# USB.net
KiCad netlist of a schematic drawn in Altium Designer
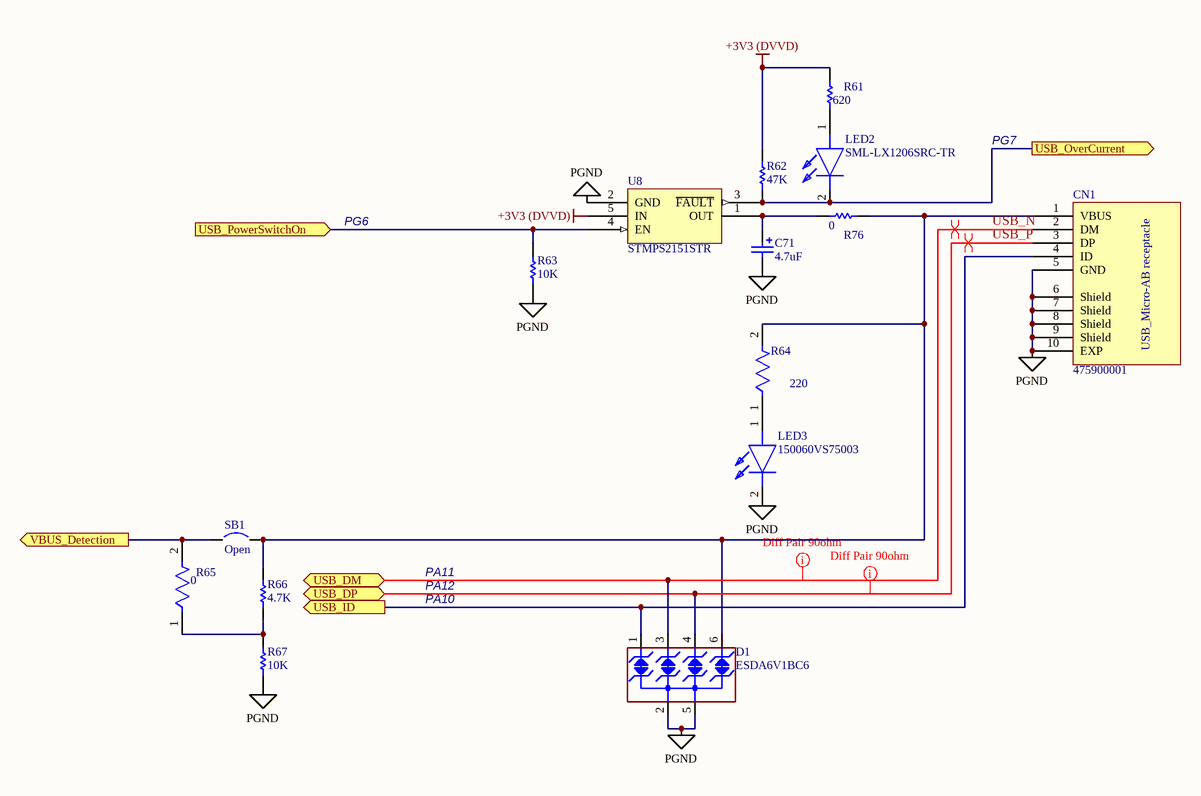
[diagram p0: USB.SchDoc]

(export (version "E")
  (design (tool "Eeschema 10.0.6"))
  (components
    (comp (ref "C71")
      (value "4.7uF")
      (footprint "Copy of MB1137:TAN-A")
      (description "Polarized Capacitor (Radial)")
      (fields (field (name "PUBLISHER") "Altium Limited"))
      (libsource (lib "Miscellaneous Devices") (part "Cap Pol1"))
    )
    (comp (ref "CN1")
      (value "475900001")
      (footprint "Copy of MB1137:MOLEX_47590001")
      (libsource (lib "Copy of MB1137") (part "475900001"))
    )
    (comp (ref "D1")
      (value "ESDA6V1BC6")
      (footprint "Copy of MB1137:3")
      (description "4-line ESD protection")
      (libsource (lib "Copy of MB1137") (part "ESDA6V1BC6"))
    )
    (comp (ref "LED2")
      (value "SML-LX1206SRC-TR")
      (footprint "SamacSys:SMLLX1206SRCTR")
      (description "LED")
      (fields (field (name "MOUSER PART NUMBER") "696-SML-LX1206SRC"))
      (libsource (lib "*") (part "SML-LX1206SRC-TR"))
    )
    (comp (ref "LED3")
      (value "150060VS75003")
      (footprint "SamacSys:150060VS75003")
      (description "LED")
      (fields (field (name "MOUSER PART NUMBER") "710-150060VS75003"))
      (libsource (lib "*") (part "150060VS75003"))
    )
    (comp (ref "R61")
      (value "620")
      (footprint "Copy of MB1137:0603R")
      (description "Resistor")
      (fields (field (name "PUBLISHER") "Altium Limited"))
      (libsource (lib "Miscellaneous Devices") (part "Res1"))
    )
    (comp (ref "R62")
      (value "47K")
      (footprint "Copy of MB1137:0603R")
      (description "Resistor")
      (fields (field (name "PUBLISHER") "Altium Limited"))
      (libsource (lib "Miscellaneous Devices") (part "res1"))
    )
    (comp (ref "R63")
      (value "10K")
      (footprint "Copy of MB1137:0603R")
      (description "Resistor")
      (fields (field (name "PUBLISHER") "Altium Limited"))
      (libsource (lib "Miscellaneous Devices") (part "Res1"))
    )
    (comp (ref "R64")
      (value "220")
      (footprint "FP-CRCW0805-e3-MFG")
      (description "RES Thick Film, 220Ω, 1%, 0.125W, 100ppm/°C, 0805")
      (fields (field (name "TOLERANCE") "1%"))
      (libsource (lib "Altium Content Vault") (part "1029c3af85768c4190bb7ad29bc67b5"))
    )
    (comp (ref "R65")
      (value "0")
      (footprint "FP-CRCW1206-MFG")
      (description "CRCW12060000ZSTA Zero Ohm Resistor, Jumper, 1206 [3216 Metric], Thick Film, 250 mW, Surface Mount")
      (libsource (lib "Altium Content Vault") (part "1029c3af85768c4190bb7ad29bc67b5"))
    )
    (comp (ref "R66")
      (value "4.7K")
      (footprint "Copy of MB1137:0603R")
      (description "Resistor")
      (fields (field (name "PUBLISHER") "Altium Limited"))
      (libsource (lib "Miscellaneous Devices") (part "res1"))
    )
    (comp (ref "R67")
      (value "10K")
      (footprint "Copy of MB1137:0603R")
      (description "Resistor")
      (fields (field (name "PUBLISHER") "Altium Limited"))
      (libsource (lib "Miscellaneous Devices") (part "res1"))
    )
    (comp (ref "R76")
      (value "0")
      (footprint "RESC2013X70X40NL20T20")
      (description "Chip Resistor, 0 Ohm, +/- 1%, 0.125 W, -55 to 155 degC, 0805 (2012 Metric), RoHS, Tape and Reel")
      (fields (field (name "PARTNUMBER") "ERJ-6GEY0R00V") (field (name "TOLERANCE") "5%"))
      (libsource (lib "Altium Content Vault") (part "RES-2"))
    )
    (comp (ref "SB1")
      (value "Open")
      (footprint "Copy of MB1137:SB_0603")
      (description "Circuit Breaker")
      (fields (field (name "PUBLISHER") "Altium Limited"))
      (libsource (lib "Copy of MB1137") (part "Circuit Breaker"))
    )
    (comp (ref "U8")
      (value "STMPS2151STR")
      (footprint "Copy of MB1137:SOT-23-5L")
      (libsource (lib "mb1045") (part "STMPS2141STR"))
    )
  )
  (nets
    (net (code "1") (name "+3V3 (DVVD)") (class "Default")
      (node (ref "R61") (pin "2") (pinfunction "2_2") (pintype "passive"))
      (node (ref "R62") (pin "1") (pinfunction "1_1") (pintype "passive"))
      (node (ref "U8") (pin "5") (pinfunction "IN_5") (pintype "passive"))
    )
    (net (code "2") (name "/USB_ID") (class "Default")
      (node (ref "CN1") (pin "4") (pinfunction "ID_4") (pintype "passive"))
      (node (ref "D1") (pin "1") (pinfunction "IO1_1") (pintype "passive"))
    )
    (net (code "3") (name "/USB_N") (class "Default")
      (node (ref "CN1") (pin "2") (pinfunction "DM_2") (pintype "passive"))
      (node (ref "D1") (pin "3") (pinfunction "GND_3") (pintype "passive"))
    )
    (net (code "4") (name "/USB_OverCurrent") (class "Default")
      (node (ref "LED2") (pin "2") (pinfunction "K_2") (pintype "passive"))
      (node (ref "R62") (pin "2") (pinfunction "2_2") (pintype "passive"))
      (node (ref "U8") (pin "3") (pinfunction "~{FAULT}_3") (pintype "output"))
    )
    (net (code "5") (name "/USB_P") (class "Default")
      (node (ref "CN1") (pin "3") (pinfunction "DP_3") (pintype "passive"))
      (node (ref "D1") (pin "4") (pinfunction "IO3_4") (pintype "passive"))
    )
    (net (code "6") (name "/USB_PowerSwitchOn") (class "Default")
      (node (ref "R63") (pin "2") (pinfunction "2_2") (pintype "passive"))
      (node (ref "U8") (pin "4") (pinfunction "EN_4") (pintype "input"))
    )
    (net (code "7") (name "/VBUS_Detection") (class "Default")
      (node (ref "R65") (pin "2") (pinfunction "2_2") (pintype "passive"))
      (node (ref "SB1") (pin "1") (pinfunction "1_1") (pintype "passive"))
    )
    (net (code "8") (name "Net-(CN1-VBUS)") (class "Default")
      (node (ref "CN1") (pin "1") (pinfunction "VBUS_1") (pintype "passive"))
      (node (ref "D1") (pin "6") (pinfunction "NC_6") (pintype "passive"))
      (node (ref "R64") (pin "2") (pinfunction "2_2") (pintype "passive"))
      (node (ref "R66") (pin "1") (pinfunction "1_1") (pintype "passive"))
      (node (ref "R76") (pin "2") (pinfunction "2_2") (pintype "passive"))
      (node (ref "SB1") (pin "2") (pinfunction "2_2") (pintype "passive"))
    )
    (net (code "9") (name "Net-(LED2-A)") (class "Default")
      (node (ref "LED2") (pin "1") (pinfunction "A_1") (pintype "passive"))
      (node (ref "R61") (pin "1") (pinfunction "1_1") (pintype "passive"))
    )
    (net (code "10") (name "Net-(LED3-A)") (class "Default")
      (node (ref "LED3") (pin "1") (pinfunction "A_1") (pintype "passive"))
      (node (ref "R64") (pin "1") (pinfunction "1_1") (pintype "passive"))
    )
    (net (code "11") (name "Net-(R65-Pad1)") (class "Default")
      (node (ref "R65") (pin "1") (pinfunction "1_1") (pintype "passive"))
      (node (ref "R66") (pin "2") (pinfunction "2_2") (pintype "passive"))
      (node (ref "R67") (pin "1") (pinfunction "1_1") (pintype "passive"))
    )
    (net (code "12") (name "Net-(U8-OUT)") (class "Default")
      (node (ref "C71") (pin "1") (pinfunction "1_1") (pintype "passive"))
      (node (ref "R76") (pin "1") (pinfunction "1_1") (pintype "passive"))
      (node (ref "U8") (pin "1") (pinfunction "OUT_1") (pintype "passive"))
    )
    (net (code "13") (name "PGND") (class "Default")
      (node (ref "C71") (pin "2") (pinfunction "2_2") (pintype "passive"))
      (node (ref "CN1") (pin "10") (pinfunction "EXP_10") (pintype "passive"))
      (node (ref "CN1") (pin "5") (pinfunction "GND_5") (pintype "passive"))
      (node (ref "CN1") (pin "6") (pinfunction "Shield_6") (pintype "passive"))
      (node (ref "CN1") (pin "7") (pinfunction "Shield_7") (pintype "passive"))
      (node (ref "CN1") (pin "8") (pinfunction "Shield_8") (pintype "passive"))
      (node (ref "CN1") (pin "9") (pinfunction "Shield_9") (pintype "passive"))
      (node (ref "D1") (pin "2") (pinfunction "IO2_2") (pintype "passive"))
      (node (ref "D1") (pin "5") (pinfunction "IO4_5") (pintype "passive"))
      (node (ref "LED3") (pin "2") (pinfunction "K_2") (pintype "passive"))
      (node (ref "R63") (pin "1") (pinfunction "1_1") (pintype "passive"))
      (node (ref "R67") (pin "2") (pinfunction "2_2") (pintype "passive"))
      (node (ref "U8") (pin "2") (pinfunction "GND_2") (pintype "passive"))
    )
  )
)
